# Sch_Ethernet.net
KiCad netlist of a schematic drawn in Altium Designer
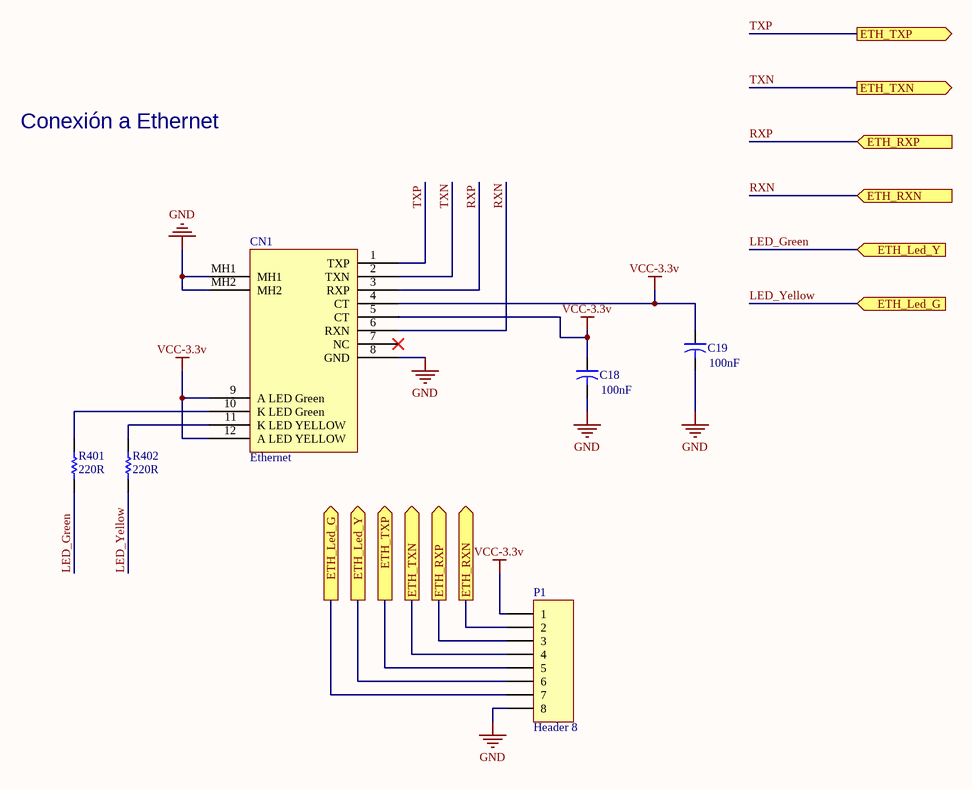
[diagram p0: Sch_Ethernet.SchDoc]

(export (version "E")
  (design (tool "Eeschema 10.0.6"))
  (components
    (comp (ref "C18")
      (value "100nF")
      (footprint "CAPR5-4X5")
      (description "Capacitor")
      (fields (field (name "Comment") "Cap2") (field (name "PUBLISHER") "Altium Limited"))
      (libsource (lib "Miscellaneous Devices") (part "Cap2"))
    )
    (comp (ref "C19")
      (value "100nF")
      (footprint "CAPR5-4X5")
      (description "Capacitor")
      (fields (field (name "Comment") "Cap2") (field (name "PUBLISHER") "Altium Limited"))
      (libsource (lib "Miscellaneous Devices") (part "Cap2"))
    )
    (comp (ref "CN1")
      (value "Ethernet")
      (footprint "RJ45")
      (description "RJ45 8pin Socket")
      (libsource (lib "Sch_Ethernet") (part "Ethernet"))
    )
    (comp (ref "P1")
      (value "Header 8")
      (footprint "HDR1X8")
      (description "Header, 8-Pin")
      (fields (field (name "PUBLISHER") "Altium Limited"))
      (libsource (lib "Miscellaneous Connectors") (part "Header 8"))
    )
    (comp (ref "R401")
      (value "220R")
      (footprint "AXIAL-0.3")
      (description "Resistor")
      (fields (field (name "Comment") "Res1") (field (name "PUBLISHER") "Altium Limited"))
      (libsource (lib "Miscellaneous Devices") (part "Res1"))
    )
    (comp (ref "R402")
      (value "220R")
      (footprint "AXIAL-0.3")
      (description "Resistor")
      (fields (field (name "Comment") "Res1") (field (name "PUBLISHER") "Altium Limited"))
      (libsource (lib "Miscellaneous Devices") (part "Res1"))
    )
  )
  (nets
    (net (code "1") (name "/LED_Green") (class "Default")
      (node (ref "P1") (pin "6") (pinfunction "6_6") (pintype "passive"))
      (node (ref "R401") (pin "1") (pinfunction "1_1") (pintype "passive"))
    )
    (net (code "2") (name "/LED_Yellow") (class "Default")
      (node (ref "P1") (pin "7") (pinfunction "7_7") (pintype "passive"))
      (node (ref "R402") (pin "1") (pinfunction "1_1") (pintype "passive"))
    )
    (net (code "3") (name "/RXN") (class "Default")
      (node (ref "CN1") (pin "6") (pinfunction "RXN_6") (pintype "passive"))
      (node (ref "P1") (pin "2") (pinfunction "2_2") (pintype "passive"))
    )
    (net (code "4") (name "/RXP") (class "Default")
      (node (ref "CN1") (pin "3") (pinfunction "RXP_3") (pintype "passive"))
      (node (ref "P1") (pin "3") (pinfunction "3_3") (pintype "passive"))
    )
    (net (code "5") (name "/TXN") (class "Default")
      (node (ref "CN1") (pin "2") (pinfunction "TXN_2") (pintype "passive"))
      (node (ref "P1") (pin "4") (pinfunction "4_4") (pintype "passive"))
    )
    (net (code "6") (name "/TXP") (class "Default")
      (node (ref "CN1") (pin "1") (pinfunction "TXP_1") (pintype "passive"))
      (node (ref "P1") (pin "5") (pinfunction "5_5") (pintype "passive"))
    )
    (net (code "7") (name "GND") (class "Default")
      (node (ref "C18") (pin "2") (pinfunction "2_2") (pintype "passive"))
      (node (ref "C19") (pin "2") (pinfunction "2_2") (pintype "passive"))
      (node (ref "CN1") (pin "8") (pinfunction "GND_8") (pintype "passive"))
      (node (ref "CN1") (pin "MH1") (pinfunction "MH1_MH1") (pintype "passive"))
      (node (ref "CN1") (pin "MH2") (pinfunction "MH2_MH2") (pintype "passive"))
      (node (ref "P1") (pin "8") (pinfunction "8_8") (pintype "passive"))
    )
    (net (code "8") (name "Net-(CN1-K_LED_Green)") (class "Default")
      (node (ref "CN1") (pin "10") (pinfunction "K_LED_Green_10") (pintype "passive"))
      (node (ref "R401") (pin "2") (pinfunction "2_2") (pintype "passive"))
    )
    (net (code "9") (name "Net-(CN1-K_LED_YELLOW)") (class "Default")
      (node (ref "CN1") (pin "11") (pinfunction "K_LED_YELLOW_11") (pintype "passive"))
      (node (ref "R402") (pin "2") (pinfunction "2_2") (pintype "passive"))
    )
    (net (code "10") (name "VCC-3.3v") (class "Default")
      (node (ref "C18") (pin "1") (pinfunction "1_1") (pintype "passive"))
      (node (ref "C19") (pin "1") (pinfunction "1_1") (pintype "passive"))
      (node (ref "CN1") (pin "12") (pinfunction "A_LED_YELLOW_12") (pintype "passive"))
      (node (ref "CN1") (pin "4") (pinfunction "CT_4") (pintype "passive"))
      (node (ref "CN1") (pin "5") (pinfunction "CT_5") (pintype "passive"))
      (node (ref "CN1") (pin "9") (pinfunction "A_LED_Green_9") (pintype "passive"))
      (node (ref "P1") (pin "1") (pinfunction "1_1") (pintype "passive"))
    )
    (net (code "11") (name "unconnected-(CN1-NC-Pad7)") (class "Default")
      (node (ref "CN1") (pin "7") (pinfunction "NC_7") (pintype "passive+no_connect"))
    )
  )
)
